# ESP8266.net
KiCad netlist of a schematic drawn in EAGLE
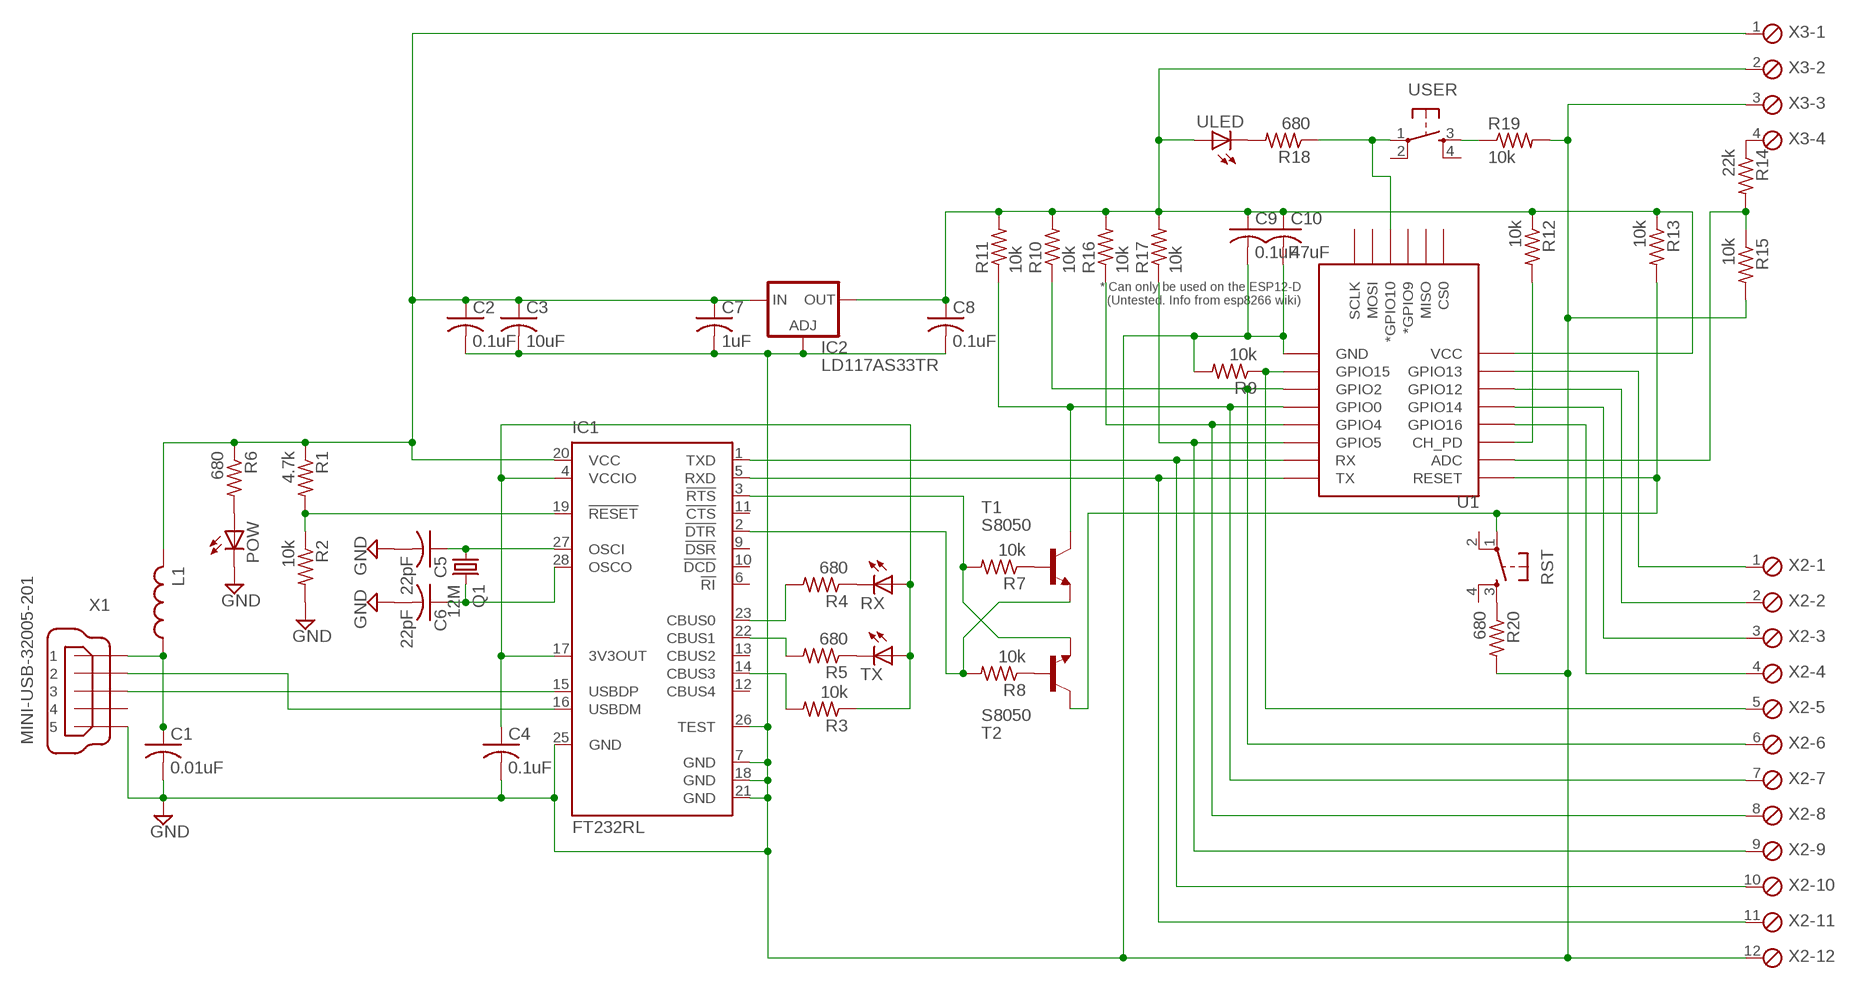
[diagram p0: schematic, sheet 1]

(export (version "E")
  (design (tool "Eeschema 10.0.6"))
  (components
    (comp (ref "C1")
      (value "0.01uF")
      (footprint "eagle-import:C0805")
      (libsource (lib "eagle-import") (part "C-USC0805"))
    )
    (comp (ref "C2")
      (value "0.1uF")
      (footprint "eagle-import:C0805")
      (libsource (lib "eagle-import") (part "C-USC0805"))
    )
    (comp (ref "C3")
      (value "10uF")
      (footprint "eagle-import:C0805")
      (libsource (lib "eagle-import") (part "C-USC0805"))
    )
    (comp (ref "C4")
      (value "0.1uF")
      (footprint "eagle-import:C0805")
      (libsource (lib "eagle-import") (part "C-USC0805"))
    )
    (comp (ref "C5")
      (value "22pF")
      (footprint "eagle-import:C0805")
      (libsource (lib "eagle-import") (part "C-USC0805"))
    )
    (comp (ref "C6")
      (value "22pF")
      (footprint "eagle-import:C0805")
      (libsource (lib "eagle-import") (part "C-USC0805"))
    )
    (comp (ref "C7")
      (value "1uF")
      (footprint "eagle-import:C0805")
      (libsource (lib "eagle-import") (part "C-USC0805"))
    )
    (comp (ref "C8")
      (value "0.1uF")
      (footprint "eagle-import:C0805")
      (libsource (lib "eagle-import") (part "C-USC0805"))
    )
    (comp (ref "C9")
      (value "0.1uF")
      (footprint "eagle-import:C0805")
      (libsource (lib "eagle-import") (part "C-USC0805"))
    )
    (comp (ref "C10")
      (value "47uF")
      (footprint "eagle-import:C0805")
      (libsource (lib "eagle-import") (part "C-USC0805"))
    )
    (comp (ref "IC1")
      (value "FT232RL")
      (footprint "eagle-import:SSOP28")
      (libsource (lib "eagle-import") (part "FT232RL"))
    )
    (comp (ref "IC2")
      (value "LD117AS33TR")
      (footprint "eagle-import:SOT223")
      (libsource (lib "eagle-import") (part "LD117A?S33TR"))
    )
    (comp (ref "L1")
      (value "L-USL2012C")
      (footprint "eagle-import:L2012C")
      (libsource (lib "eagle-import") (part "L-USL2012C"))
    )
    (comp (ref "POW")
      (value "LEDCHIP-LED0805")
      (footprint "eagle-import:CHIP-LED0805")
      (libsource (lib "eagle-import") (part "LEDCHIP-LED0805"))
    )
    (comp (ref "Q1")
      (value "12M")
      (footprint "eagle-import:SM49")
      (libsource (lib "eagle-import") (part "CRYSTALSM49"))
    )
    (comp (ref "R1")
      (value "4.7k")
      (footprint "eagle-import:R0805")
      (libsource (lib "eagle-import") (part "R-US_R0805"))
    )
    (comp (ref "R2")
      (value "10k")
      (footprint "eagle-import:R0805")
      (libsource (lib "eagle-import") (part "R-US_R0805"))
    )
    (comp (ref "R3")
      (value "10k")
      (footprint "eagle-import:R0805")
      (libsource (lib "eagle-import") (part "R-US_R0805"))
    )
    (comp (ref "R4")
      (value "680")
      (footprint "eagle-import:R0805")
      (libsource (lib "eagle-import") (part "R-US_R0805"))
    )
    (comp (ref "R5")
      (value "680")
      (footprint "eagle-import:R0805")
      (libsource (lib "eagle-import") (part "R-US_R0805"))
    )
    (comp (ref "R6")
      (value "680")
      (footprint "eagle-import:R0805")
      (libsource (lib "eagle-import") (part "R-US_R0805"))
    )
    (comp (ref "R7")
      (value "10k")
      (footprint "eagle-import:R0805")
      (libsource (lib "eagle-import") (part "R-US_R0805"))
    )
    (comp (ref "R8")
      (value "10k")
      (footprint "eagle-import:R0805")
      (libsource (lib "eagle-import") (part "R-US_R0805"))
    )
    (comp (ref "R9")
      (value "10k")
      (footprint "eagle-import:R0805")
      (libsource (lib "eagle-import") (part "R-US_R0805"))
    )
    (comp (ref "R10")
      (value "10k")
      (footprint "eagle-import:R0805")
      (libsource (lib "eagle-import") (part "R-US_R0805"))
    )
    (comp (ref "R11")
      (value "10k")
      (footprint "eagle-import:R0805")
      (libsource (lib "eagle-import") (part "R-US_R0805"))
    )
    (comp (ref "R12")
      (value "10k")
      (footprint "eagle-import:R0805")
      (libsource (lib "eagle-import") (part "R-US_R0805"))
    )
    (comp (ref "R13")
      (value "10k")
      (footprint "eagle-import:R0805")
      (libsource (lib "eagle-import") (part "R-US_R0805"))
    )
    (comp (ref "R14")
      (value "22k")
      (footprint "eagle-import:R0805")
      (libsource (lib "eagle-import") (part "R-US_R0805"))
    )
    (comp (ref "R15")
      (value "10k")
      (footprint "eagle-import:R0805")
      (libsource (lib "eagle-import") (part "R-US_R0805"))
    )
    (comp (ref "R16")
      (value "10k")
      (footprint "eagle-import:R0805")
      (libsource (lib "eagle-import") (part "R-US_R0805"))
    )
    (comp (ref "R17")
      (value "10k")
      (footprint "eagle-import:R0805")
      (libsource (lib "eagle-import") (part "R-US_R0805"))
    )
    (comp (ref "R18")
      (value "680")
      (footprint "eagle-import:R0805")
      (libsource (lib "eagle-import") (part "R-US_R0805"))
    )
    (comp (ref "R19")
      (value "10k")
      (footprint "eagle-import:R0805")
      (libsource (lib "eagle-import") (part "R-US_R0805"))
    )
    (comp (ref "R20")
      (value "680")
      (footprint "eagle-import:R0805")
      (libsource (lib "eagle-import") (part "R-US_R0805"))
    )
    (comp (ref "RST")
      (value "DTSM-6")
      (footprint "eagle-import:DTSM-6")
      (libsource (lib "eagle-import") (part "DTSM-6"))
    )
    (comp (ref "RX")
      (value "LEDCHIP-LED0805")
      (footprint "eagle-import:CHIP-LED0805")
      (libsource (lib "eagle-import") (part "LEDCHIP-LED0805"))
    )
    (comp (ref "T1")
      (value "S8050")
      (footprint "eagle-import:SOT23-BEC")
      (libsource (lib "eagle-import") (part "-NPN-SOT23-BECMMBT2222ALT1"))
    )
    (comp (ref "T2")
      (value "S8050")
      (footprint "eagle-import:SOT23-BEC")
      (libsource (lib "eagle-import") (part "-NPN-SOT23-BECMMBT2222ALT1"))
    )
    (comp (ref "TX")
      (value "LEDCHIP-LED0805")
      (footprint "eagle-import:CHIP-LED0805")
      (libsource (lib "eagle-import") (part "LEDCHIP-LED0805"))
    )
    (comp (ref "U1")
      (value "ESP12ESMD")
      (footprint "eagle-import:ESP12E-SMD")
      (libsource (lib "eagle-import") (part "ESP12ESMD"))
    )
    (comp (ref "ULED")
      (value "LEDCHIP-LED0805")
      (footprint "eagle-import:CHIP-LED0805")
      (libsource (lib "eagle-import") (part "LEDCHIP-LED0805"))
    )
    (comp (ref "USER")
      (value "DTSM-6")
      (footprint "eagle-import:DTSM-6")
      (libsource (lib "eagle-import") (part "DTSM-6"))
    )
    (comp (ref "X1")
      (value "MINI-USB-32005-201")
      (footprint "eagle-import:32005-201")
      (libsource (lib "eagle-import") (part "MINI-USB-32005-201"))
    )
    (comp (ref "X2")
      (value "MPT12")
      (footprint "eagle-import:12POL254")
      (libsource (lib "eagle-import") (part "MPT12"))
    )
    (comp (ref "X3")
      (value "MPT4")
      (footprint "eagle-import:4POL254")
      (libsource (lib "eagle-import") (part "MPT4"))
    )
  )
  (nets
    (net (code "1") (name "GND") (class "Default")
      (node (ref "C1") (pin "2") (pinfunction "2_2") (pintype "passive"))
      (node (ref "C10") (pin "2") (pinfunction "2_2") (pintype "passive"))
      (node (ref "C2") (pin "2") (pinfunction "2_2") (pintype "passive"))
      (node (ref "C3") (pin "2") (pinfunction "2_2") (pintype "passive"))
      (node (ref "C4") (pin "2") (pinfunction "2_2") (pintype "passive"))
      (node (ref "C5") (pin "2") (pinfunction "2_2") (pintype "passive"))
      (node (ref "C6") (pin "2") (pinfunction "2_2") (pintype "passive"))
      (node (ref "C7") (pin "2") (pinfunction "2_2") (pintype "passive"))
      (node (ref "C8") (pin "2") (pinfunction "2_2") (pintype "passive"))
      (node (ref "C9") (pin "2") (pinfunction "2_2") (pintype "passive"))
      (node (ref "IC1") (pin "18") (pinfunction "GND_18") (pintype "power_in"))
      (node (ref "IC1") (pin "21") (pinfunction "GND_21") (pintype "power_in"))
      (node (ref "IC1") (pin "25") (pinfunction "GND_25") (pintype "power_in"))
      (node (ref "IC1") (pin "26") (pinfunction "TEST_26") (pintype "input"))
      (node (ref "IC1") (pin "7") (pinfunction "GND_7") (pintype "power_in"))
      (node (ref "IC2") (pin "1") (pinfunction "ADJ_1") (pintype "input"))
      (node (ref "POW") (pin "C") (pinfunction "C_C") (pintype "passive"))
      (node (ref "R15") (pin "2") (pinfunction "2_2") (pintype "passive"))
      (node (ref "R19") (pin "2") (pinfunction "2_2") (pintype "passive"))
      (node (ref "R2") (pin "2") (pinfunction "2_2") (pintype "passive"))
      (node (ref "R20") (pin "2") (pinfunction "2_2") (pintype "passive"))
      (node (ref "R9") (pin "2") (pinfunction "2_2") (pintype "passive"))
      (node (ref "U1") (pin "GND") (pinfunction "GND_GND") (pintype "bidirectional"))
      (node (ref "X1") (pin "5") (pinfunction "5_5") (pintype "passive"))
      (node (ref "X2") (pin "12") (pinfunction "1_12") (pintype "passive"))
      (node (ref "X3") (pin "3") (pinfunction "1_3") (pintype "passive"))
    )
    (net (code "2") (name "Net-(C1-Pad1)") (class "Default")
      (node (ref "C1") (pin "1") (pinfunction "1_1") (pintype "passive"))
      (node (ref "L1") (pin "1") (pinfunction "1_1") (pintype "passive"))
      (node (ref "X1") (pin "1") (pinfunction "1_1") (pintype "passive"))
    )
    (net (code "3") (name "Net-(IC1-3V3OUT)") (class "Default")
      (node (ref "C4") (pin "1") (pinfunction "1_1") (pintype "passive"))
      (node (ref "IC1") (pin "17") (pinfunction "3V3OUT_17") (pintype "output"))
      (node (ref "IC1") (pin "4") (pinfunction "VCCIO_4") (pintype "power_in"))
      (node (ref "R3") (pin "1") (pinfunction "1_1") (pintype "passive"))
      (node (ref "RX") (pin "A") (pinfunction "A_A") (pintype "passive"))
      (node (ref "TX") (pin "A") (pinfunction "A_A") (pintype "passive"))
    )
    (net (code "4") (name "Net-(IC1-CBUS0)") (class "Default")
      (node (ref "IC1") (pin "23") (pinfunction "CBUS0_23") (pintype "bidirectional"))
      (node (ref "R4") (pin "2") (pinfunction "2_2") (pintype "passive"))
    )
    (net (code "5") (name "Net-(IC1-CBUS1)") (class "Default")
      (node (ref "IC1") (pin "22") (pinfunction "CBUS1_22") (pintype "bidirectional"))
      (node (ref "R5") (pin "2") (pinfunction "2_2") (pintype "passive"))
    )
    (net (code "6") (name "Net-(IC1-CBUS3)") (class "Default")
      (node (ref "IC1") (pin "14") (pinfunction "CBUS3_14") (pintype "bidirectional"))
      (node (ref "R3") (pin "2") (pinfunction "2_2") (pintype "passive"))
    )
    (net (code "7") (name "Net-(IC1-OSCI)") (class "Default")
      (node (ref "C5") (pin "1") (pinfunction "1_1") (pintype "passive"))
      (node (ref "IC1") (pin "27") (pinfunction "OSCI_27") (pintype "input"))
      (node (ref "Q1") (pin "1") (pinfunction "1_1") (pintype "passive"))
    )
    (net (code "8") (name "Net-(IC1-OSCO)") (class "Default")
      (node (ref "C6") (pin "1") (pinfunction "1_1") (pintype "passive"))
      (node (ref "IC1") (pin "28") (pinfunction "OSCO_28") (pintype "output"))
      (node (ref "Q1") (pin "2") (pinfunction "2_2") (pintype "passive"))
    )
    (net (code "9") (name "Net-(IC1-RXD)") (class "Default")
      (node (ref "IC1") (pin "5") (pinfunction "RXD_5") (pintype "input"))
      (node (ref "U1") (pin "TXD0") (pinfunction "TX_TXD0") (pintype "bidirectional"))
      (node (ref "X2") (pin "11") (pinfunction "1_11") (pintype "passive"))
    )
    (net (code "10") (name "Net-(IC1-TXD)") (class "Default")
      (node (ref "IC1") (pin "1") (pinfunction "TXD_1") (pintype "output"))
      (node (ref "U1") (pin "RXD0") (pinfunction "RX_RXD0") (pintype "bidirectional"))
      (node (ref "X2") (pin "10") (pinfunction "1_10") (pintype "passive"))
    )
    (net (code "11") (name "Net-(IC1-USBDM)") (class "Default")
      (node (ref "IC1") (pin "16") (pinfunction "USBDM_16") (pintype "bidirectional"))
      (node (ref "X1") (pin "2") (pinfunction "2_2") (pintype "passive"))
    )
    (net (code "12") (name "Net-(IC1-USBDP)") (class "Default")
      (node (ref "IC1") (pin "15") (pinfunction "USBDP_15") (pintype "bidirectional"))
      (node (ref "X1") (pin "3") (pinfunction "3_3") (pintype "passive"))
    )
    (net (code "13") (name "Net-(IC1-VCC)") (class "Default")
      (node (ref "C2") (pin "1") (pinfunction "1_1") (pintype "passive"))
      (node (ref "C3") (pin "1") (pinfunction "1_1") (pintype "passive"))
      (node (ref "C7") (pin "1") (pinfunction "1_1") (pintype "passive"))
      (node (ref "IC1") (pin "20") (pinfunction "VCC_20") (pintype "power_in"))
      (node (ref "IC2") (pin "3") (pinfunction "IN_3") (pintype "input"))
      (node (ref "L1") (pin "2") (pinfunction "2_2") (pintype "passive"))
      (node (ref "R1") (pin "1") (pinfunction "1_1") (pintype "passive"))
      (node (ref "R6") (pin "1") (pinfunction "1_1") (pintype "passive"))
      (node (ref "X3") (pin "1") (pinfunction "1_1") (pintype "passive"))
    )
    (net (code "14") (name "Net-(IC1-~{DTR})") (class "Default")
      (node (ref "IC1") (pin "2") (pinfunction "~{DTR}_2") (pintype "output"))
      (node (ref "R8") (pin "2") (pinfunction "2_2") (pintype "passive"))
      (node (ref "T1") (pin "E") (pinfunction "E_E") (pintype "passive"))
    )
    (net (code "15") (name "Net-(IC1-~{RESET})") (class "Default")
      (node (ref "IC1") (pin "19") (pinfunction "~{RESET}_19") (pintype "input"))
      (node (ref "R1") (pin "2") (pinfunction "2_2") (pintype "passive"))
      (node (ref "R2") (pin "1") (pinfunction "1_1") (pintype "passive"))
    )
    (net (code "16") (name "Net-(IC1-~{RTS})") (class "Default")
      (node (ref "IC1") (pin "3") (pinfunction "~{RTS}_3") (pintype "output"))
      (node (ref "R7") (pin "2") (pinfunction "2_2") (pintype "passive"))
      (node (ref "T2") (pin "E") (pinfunction "E_E") (pintype "passive"))
    )
    (net (code "17") (name "Net-(IC2-OUT)") (class "Default")
      (node (ref "C10") (pin "1") (pinfunction "1_1") (pintype "passive"))
      (node (ref "C8") (pin "1") (pinfunction "1_1") (pintype "passive"))
      (node (ref "C9") (pin "1") (pinfunction "1_1") (pintype "passive"))
      (node (ref "IC2") (pin "4") (pinfunction "OUT_4") (pintype "passive"))
      (node (ref "R10") (pin "2") (pinfunction "2_2") (pintype "passive"))
      (node (ref "R11") (pin "2") (pinfunction "2_2") (pintype "passive"))
      (node (ref "R12") (pin "1") (pinfunction "1_1") (pintype "passive"))
      (node (ref "R13") (pin "1") (pinfunction "1_1") (pintype "passive"))
      (node (ref "R16") (pin "2") (pinfunction "2_2") (pintype "passive"))
      (node (ref "R17") (pin "2") (pinfunction "2_2") (pintype "passive"))
      (node (ref "U1") (pin "VCC") (pinfunction "VCC_VCC") (pintype "bidirectional"))
      (node (ref "ULED") (pin "A") (pinfunction "A_A") (pintype "passive"))
      (node (ref "X3") (pin "2") (pinfunction "1_2") (pintype "passive"))
    )
    (net (code "18") (name "Net-(POW-PadA)") (class "Default")
      (node (ref "POW") (pin "A") (pinfunction "A_A") (pintype "passive"))
      (node (ref "R6") (pin "2") (pinfunction "2_2") (pintype "passive"))
    )
    (net (code "19") (name "Net-(R4-Pad1)") (class "Default")
      (node (ref "R4") (pin "1") (pinfunction "1_1") (pintype "passive"))
      (node (ref "RX") (pin "C") (pinfunction "C_C") (pintype "passive"))
    )
    (net (code "20") (name "Net-(R5-Pad1)") (class "Default")
      (node (ref "R5") (pin "1") (pinfunction "1_1") (pintype "passive"))
      (node (ref "TX") (pin "C") (pinfunction "C_C") (pintype "passive"))
    )
    (net (code "21") (name "Net-(R7-Pad1)") (class "Default")
      (node (ref "R7") (pin "1") (pinfunction "1_1") (pintype "passive"))
      (node (ref "T1") (pin "B") (pinfunction "B_B") (pintype "passive"))
    )
    (net (code "22") (name "Net-(R8-Pad1)") (class "Default")
      (node (ref "R8") (pin "1") (pinfunction "1_1") (pintype "passive"))
      (node (ref "T2") (pin "B") (pinfunction "B_B") (pintype "passive"))
    )
    (net (code "23") (name "Net-(R12-Pad2)") (class "Default")
      (node (ref "R12") (pin "2") (pinfunction "2_2") (pintype "passive"))
      (node (ref "U1") (pin "CH_PD") (pinfunction "CH_PD_CH_PD") (pintype "bidirectional"))
    )
    (net (code "24") (name "Net-(R13-Pad2)") (class "Default")
      (node (ref "R13") (pin "2") (pinfunction "2_2") (pintype "passive"))
      (node (ref "RST") (pin "1") (pinfunction "1_1") (pintype "passive"))
      (node (ref "T2") (pin "C") (pinfunction "C_C") (pintype "passive"))
      (node (ref "U1") (pin "RESET") (pinfunction "RESET_RESET") (pintype "bidirectional"))
    )
    (net (code "25") (name "Net-(R14-Pad2)") (class "Default")
      (node (ref "R14") (pin "2") (pinfunction "2_2") (pintype "passive"))
      (node (ref "R15") (pin "1") (pinfunction "1_1") (pintype "passive"))
      (node (ref "U1") (pin "ADC") (pinfunction "ADC_ADC") (pintype "bidirectional"))
    )
    (net (code "26") (name "Net-(R18-Pad2)") (class "Default")
      (node (ref "R18") (pin "2") (pinfunction "2_2") (pintype "passive"))
      (node (ref "ULED") (pin "C") (pinfunction "C_C") (pintype "passive"))
    )
    (net (code "27") (name "Net-(R19-Pad1)") (class "Default")
      (node (ref "R19") (pin "1") (pinfunction "1_1") (pintype "passive"))
      (node (ref "USER") (pin "3") (pinfunction "3_3") (pintype "passive"))
    )
    (net (code "28") (name "Net-(R20-Pad1)") (class "Default")
      (node (ref "R20") (pin "1") (pinfunction "1_1") (pintype "passive"))
      (node (ref "RST") (pin "3") (pinfunction "3_3") (pintype "passive"))
    )
    (net (code "29") (name "Net-(U1-*GPIO10)") (class "Default")
      (node (ref "R18") (pin "1") (pinfunction "1_1") (pintype "passive"))
      (node (ref "U1") (pin "GPIO10") (pinfunction "*GPIO10_GPIO10") (pintype "bidirectional"))
      (node (ref "USER") (pin "1") (pinfunction "1_1") (pintype "passive"))
    )
    (net (code "30") (name "Net-(U1-PadGPIO13)") (class "Default")
      (node (ref "U1") (pin "GPIO13") (pinfunction "GPIO13_GPIO13") (pintype "bidirectional"))
      (node (ref "X2") (pin "1") (pinfunction "1_1") (pintype "passive"))
    )
    (net (code "31") (name "Net-(X2E-1)") (class "Default")
      (node (ref "U1") (pin "GPIO12") (pinfunction "GPIO12_GPIO12") (pintype "bidirectional"))
      (node (ref "X2") (pin "2") (pinfunction "1_2") (pintype "passive"))
    )
    (net (code "32") (name "Net-(X2F-1)") (class "Default")
      (node (ref "U1") (pin "GPIO14") (pinfunction "GPIO14_GPIO14") (pintype "bidirectional"))
      (node (ref "X2") (pin "3") (pinfunction "1_3") (pintype "passive"))
    )
    (net (code "33") (name "Net-(X2G-1)") (class "Default")
      (node (ref "U1") (pin "GPIO16") (pinfunction "GPIO16_GPIO16") (pintype "bidirectional"))
      (node (ref "X2") (pin "4") (pinfunction "1_4") (pintype "passive"))
    )
    (net (code "34") (name "Net-(X2H-1)") (class "Default")
      (node (ref "R9") (pin "1") (pinfunction "1_1") (pintype "passive"))
      (node (ref "U1") (pin "GPIO15") (pinfunction "GPIO15_GPIO15") (pintype "bidirectional"))
      (node (ref "X2") (pin "5") (pinfunction "1_5") (pintype "passive"))
    )
    (net (code "35") (name "Net-(X2I-1)") (class "Default")
      (node (ref "R10") (pin "1") (pinfunction "1_1") (pintype "passive"))
      (node (ref "U1") (pin "GPIO2") (pinfunction "GPIO2_GPIO2") (pintype "bidirectional"))
      (node (ref "X2") (pin "6") (pinfunction "1_6") (pintype "passive"))
    )
    (net (code "36") (name "Net-(X2J-1)") (class "Default")
      (node (ref "R11") (pin "1") (pinfunction "1_1") (pintype "passive"))
      (node (ref "T1") (pin "C") (pinfunction "C_C") (pintype "passive"))
      (node (ref "U1") (pin "GPIO0") (pinfunction "GPIO0_GPIO0") (pintype "bidirectional"))
      (node (ref "X2") (pin "7") (pinfunction "1_7") (pintype "passive"))
    )
    (net (code "37") (name "Net-(X2K-1)") (class "Default")
      (node (ref "R16") (pin "1") (pinfunction "1_1") (pintype "passive"))
      (node (ref "U1") (pin "GPIO4") (pinfunction "GPIO4_GPIO4") (pintype "bidirectional"))
      (node (ref "X2") (pin "8") (pinfunction "1_8") (pintype "passive"))
    )
    (net (code "38") (name "Net-(X2L-1)") (class "Default")
      (node (ref "R17") (pin "1") (pinfunction "1_1") (pintype "passive"))
      (node (ref "U1") (pin "GPIO5") (pinfunction "GPIO5_GPIO5") (pintype "bidirectional"))
      (node (ref "X2") (pin "9") (pinfunction "1_9") (pintype "passive"))
    )
    (net (code "39") (name "Net-(X3D-1)") (class "Default")
      (node (ref "R14") (pin "1") (pinfunction "1_1") (pintype "passive"))
      (node (ref "X3") (pin "4") (pinfunction "1_4") (pintype "passive"))
    )
    (net (code "40") (name "unconnected-(IC1-CBUS2-Pad13)") (class "Default")
      (node (ref "IC1") (pin "13") (pinfunction "CBUS2_13") (pintype "bidirectional"))
    )
    (net (code "41") (name "unconnected-(IC1-CBUS4-Pad12)") (class "Default")
      (node (ref "IC1") (pin "12") (pinfunction "CBUS4_12") (pintype "bidirectional"))
    )
    (net (code "42") (name "unconnected-(IC1-~{CTS}-Pad11)") (class "Default")
      (node (ref "IC1") (pin "11") (pinfunction "~{CTS}_11") (pintype "input"))
    )
    (net (code "43") (name "unconnected-(IC1-~{DCD}-Pad10)") (class "Default")
      (node (ref "IC1") (pin "10") (pinfunction "~{DCD}_10") (pintype "input"))
    )
    (net (code "44") (name "unconnected-(IC1-~{DSR}-Pad9)") (class "Default")
      (node (ref "IC1") (pin "9") (pinfunction "~{DSR}_9") (pintype "input"))
    )
    (net (code "45") (name "unconnected-(IC1-~{RI}-Pad6)") (class "Default")
      (node (ref "IC1") (pin "6") (pinfunction "~{RI}_6") (pintype "input"))
    )
    (net (code "46") (name "unconnected-(RST-Pad2)") (class "Default")
      (node (ref "RST") (pin "2") (pinfunction "2_2") (pintype "passive"))
    )
    (net (code "47") (name "unconnected-(RST-Pad4)") (class "Default")
      (node (ref "RST") (pin "4") (pinfunction "4_4") (pintype "passive"))
    )
    (net (code "48") (name "unconnected-(U1-*GPIO9-PadGPIO9)") (class "Default")
      (node (ref "U1") (pin "GPIO9") (pinfunction "*GPIO9_GPIO9") (pintype "bidirectional"))
    )
    (net (code "49") (name "unconnected-(U1-PadCS0)") (class "Default")
      (node (ref "U1") (pin "CS0") (pinfunction "CS0_CS0") (pintype "bidirectional"))
    )
    (net (code "50") (name "unconnected-(U1-PadMISO)") (class "Default")
      (node (ref "U1") (pin "MISO") (pinfunction "MISO_MISO") (pintype "bidirectional"))
    )
    (net (code "51") (name "unconnected-(U1-PadMOSI)") (class "Default")
      (node (ref "U1") (pin "MOSI") (pinfunction "MOSI_MOSI") (pintype "bidirectional"))
    )
    (net (code "52") (name "unconnected-(U1-PadSCLK)") (class "Default")
      (node (ref "U1") (pin "SCLK") (pinfunction "SCLK_SCLK") (pintype "bidirectional"))
    )
    (net (code "53") (name "unconnected-(USER-Pad2)") (class "Default")
      (node (ref "USER") (pin "2") (pinfunction "2_2") (pintype "passive"))
    )
    (net (code "54") (name "unconnected-(USER-Pad4)") (class "Default")
      (node (ref "USER") (pin "4") (pinfunction "4_4") (pintype "passive"))
    )
    (net (code "55") (name "unconnected-(X1-Pad4)") (class "Default")
      (node (ref "X1") (pin "4") (pinfunction "4_4") (pintype "passive"))
    )
  )
)
